# HMI.net
KiCad netlist of a schematic drawn in Altium Designer
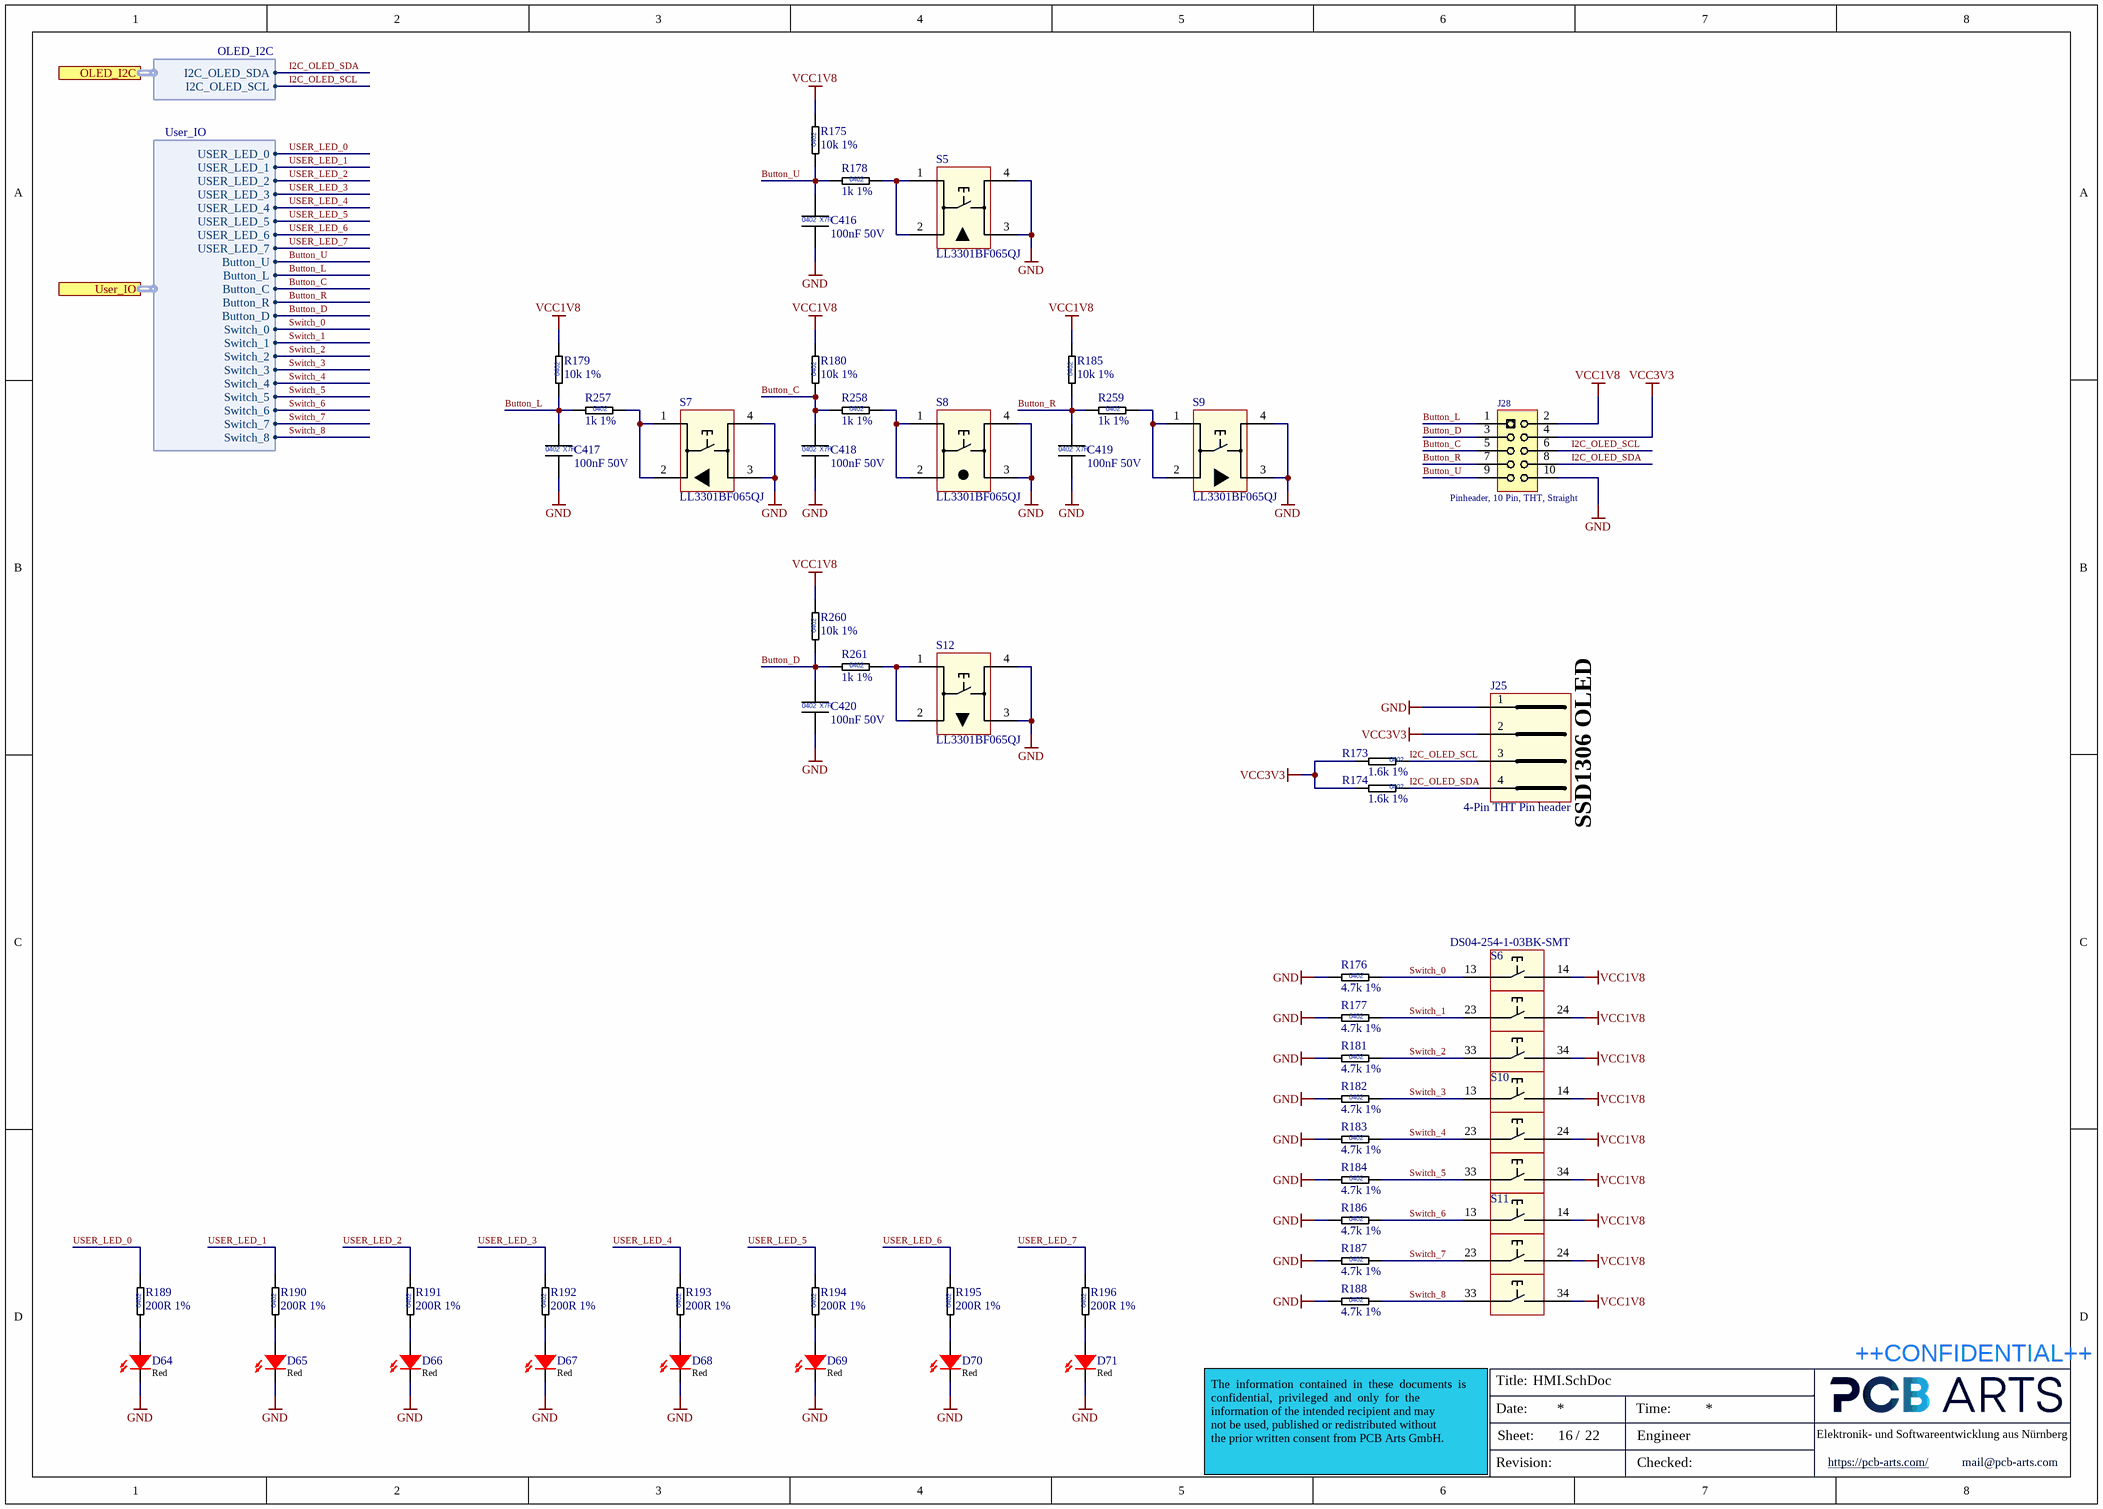
[diagram p0: HMI.SchDoc]

(export (version "E")
  (design (tool "Eeschema 10.0.6"))
  (components
    (comp (ref "C416")
      (value "100nF 50V")
      (footprint "Cap:CAP_0402_L")
      (description "Multilayer Ceramic Capacitors MLCC - SMD/SMT 0402 50VDC")
      (libsource (lib "Cap") (part "CAP_0402_100nF_50V"))
    )
    (comp (ref "C417")
      (value "100nF 50V")
      (footprint "Cap:CAP_0402_L")
      (description "Multilayer Ceramic Capacitors MLCC - SMD/SMT 0402 50VDC")
      (libsource (lib "Cap") (part "CAP_0402_100nF_50V"))
    )
    (comp (ref "C418")
      (value "100nF 50V")
      (footprint "Cap:CAP_0402_L")
      (description "Multilayer Ceramic Capacitors MLCC - SMD/SMT 0402 50VDC")
      (libsource (lib "Cap") (part "CAP_0402_100nF_50V"))
    )
    (comp (ref "C419")
      (value "100nF 50V")
      (footprint "Cap:CAP_0402_L")
      (description "Multilayer Ceramic Capacitors MLCC - SMD/SMT 0402 50VDC")
      (libsource (lib "Cap") (part "CAP_0402_100nF_50V"))
    )
    (comp (ref "C420")
      (value "100nF 50V")
      (footprint "Cap:CAP_0402_L")
      (description "Multilayer Ceramic Capacitors MLCC - SMD/SMT 0402 50VDC")
      (libsource (lib "Cap") (part "CAP_0402_100nF_50V"))
    )
    (comp (ref "D64")
      (value "LTST-S270KRKT")
      (footprint "Active:LED-0603 Sideview")
      (description "RED  0603 Light Emitting Diode")
      (fields (field (name "COLOR") "Red"))
      (libsource (lib "Active") (part "LED 0603 Red Sideview"))
    )
    (comp (ref "D65")
      (value "LTST-S270KRKT")
      (footprint "Active:LED-0603 Sideview")
      (description "RED  0603 Light Emitting Diode")
      (fields (field (name "COLOR") "Red"))
      (libsource (lib "Active") (part "LED 0603 Red Sideview"))
    )
    (comp (ref "D66")
      (value "LTST-S270KRKT")
      (footprint "Active:LED-0603 Sideview")
      (description "RED  0603 Light Emitting Diode")
      (fields (field (name "COLOR") "Red"))
      (libsource (lib "Active") (part "LED 0603 Red Sideview"))
    )
    (comp (ref "D67")
      (value "LTST-S270KRKT")
      (footprint "Active:LED-0603 Sideview")
      (description "RED  0603 Light Emitting Diode")
      (fields (field (name "COLOR") "Red"))
      (libsource (lib "Active") (part "LED 0603 Red Sideview"))
    )
    (comp (ref "D68")
      (value "LTST-S270KRKT")
      (footprint "Active:LED-0603 Sideview")
      (description "RED  0603 Light Emitting Diode")
      (fields (field (name "COLOR") "Red"))
      (libsource (lib "Active") (part "LED 0603 Red Sideview"))
    )
    (comp (ref "D69")
      (value "LTST-S270KRKT")
      (footprint "Active:LED-0603 Sideview")
      (description "RED  0603 Light Emitting Diode")
      (fields (field (name "COLOR") "Red"))
      (libsource (lib "Active") (part "LED 0603 Red Sideview"))
    )
    (comp (ref "D70")
      (value "LTST-S270KRKT")
      (footprint "Active:LED-0603 Sideview")
      (description "RED  0603 Light Emitting Diode")
      (fields (field (name "COLOR") "Red"))
      (libsource (lib "Active") (part "LED 0603 Red Sideview"))
    )
    (comp (ref "D71")
      (value "LTST-S270KRKT")
      (footprint "Active:LED-0603 Sideview")
      (description "RED  0603 Light Emitting Diode")
      (fields (field (name "COLOR") "Red"))
      (libsource (lib "Active") (part "LED 0603 Red Sideview"))
    )
    (comp (ref "J25")
      (value "4-Pin THT Pin header")
      (footprint "Conn:61300411121")
      (description "WR-PHD 2.54mm 4Pin THT Header")
      (libsource (lib "Conn") (part "61300411121_WR-PHD 2.54mm 4Pin THT Header"))
    )
    (comp (ref "J28")
      (value "Pinheader, 10 Pin, THT, Straight")
      (footprint "Conn:62701021621")
      (description "Box Pin header THT 1.27mm 10Pol Straight")
      (libsource (lib "Conn") (part "62701021621_Box Pin header THT 1.27mm 10Pol Straight"))
    )
    (comp (ref "R173")
      (value "1.6k 1%")
      (footprint "Res:RES_0402_L")
      (description "Thick Film Resistors - SMD 1.6kOhm 1%")
      (libsource (lib "Res") (part "RES_0402_1.6k_1%"))
    )
    (comp (ref "R174")
      (value "1.6k 1%")
      (footprint "Res:RES_0402_L")
      (description "Thick Film Resistors - SMD 1.6kOhm 1%")
      (libsource (lib "Res") (part "RES_0402_1.6k_1%"))
    )
    (comp (ref "R175")
      (value "10k 1%")
      (footprint "Res:RES_0402_L")
      (description "Thick Film Resistors - SMD 10kOhm 1%")
      (libsource (lib "Res") (part "RES_0402_10k_1%"))
    )
    (comp (ref "R176")
      (value "4.7k 1%")
      (footprint "Res:RES_0402_L")
      (description "Thick Film Resistors - SMD 4.7kOhm 1%")
      (libsource (lib "Res") (part "RES_0402_4.7k_1%"))
    )
    (comp (ref "R177")
      (value "4.7k 1%")
      (footprint "Res:RES_0402_L")
      (description "Thick Film Resistors - SMD 4.7kOhm 1%")
      (libsource (lib "Res") (part "RES_0402_4.7k_1%"))
    )
    (comp (ref "R178")
      (value "1k 1%")
      (footprint "Res:RES_0402_L")
      (description "Thick Film Resistors - SMD 1kOhm 1%")
      (libsource (lib "Res") (part "RES_0402_1k_1%"))
    )
    (comp (ref "R179")
      (value "10k 1%")
      (footprint "Res:RES_0402_L")
      (description "Thick Film Resistors - SMD 10kOhm 1%")
      (libsource (lib "Res") (part "RES_0402_10k_1%"))
    )
    (comp (ref "R180")
      (value "10k 1%")
      (footprint "Res:RES_0402_L")
      (description "Thick Film Resistors - SMD 10kOhm 1%")
      (libsource (lib "Res") (part "RES_0402_10k_1%"))
    )
    (comp (ref "R181")
      (value "4.7k 1%")
      (footprint "Res:RES_0402_L")
      (description "Thick Film Resistors - SMD 4.7kOhm 1%")
      (libsource (lib "Res") (part "RES_0402_4.7k_1%"))
    )
    (comp (ref "R182")
      (value "4.7k 1%")
      (footprint "Res:RES_0402_L")
      (description "Thick Film Resistors - SMD 4.7kOhm 1%")
      (libsource (lib "Res") (part "RES_0402_4.7k_1%"))
    )
    (comp (ref "R183")
      (value "4.7k 1%")
      (footprint "Res:RES_0402_L")
      (description "Thick Film Resistors - SMD 4.7kOhm 1%")
      (libsource (lib "Res") (part "RES_0402_4.7k_1%"))
    )
    (comp (ref "R184")
      (value "4.7k 1%")
      (footprint "Res:RES_0402_L")
      (description "Thick Film Resistors - SMD 4.7kOhm 1%")
      (libsource (lib "Res") (part "RES_0402_4.7k_1%"))
    )
    (comp (ref "R185")
      (value "10k 1%")
      (footprint "Res:RES_0402_L")
      (description "Thick Film Resistors - SMD 10kOhm 1%")
      (libsource (lib "Res") (part "RES_0402_10k_1%"))
    )
    (comp (ref "R186")
      (value "4.7k 1%")
      (footprint "Res:RES_0402_L")
      (description "Thick Film Resistors - SMD 4.7kOhm 1%")
      (libsource (lib "Res") (part "RES_0402_4.7k_1%"))
    )
    (comp (ref "R187")
      (value "4.7k 1%")
      (footprint "Res:RES_0402_L")
      (description "Thick Film Resistors - SMD 4.7kOhm 1%")
      (libsource (lib "Res") (part "RES_0402_4.7k_1%"))
    )
    (comp (ref "R188")
      (value "4.7k 1%")
      (footprint "Res:RES_0402_L")
      (description "Thick Film Resistors - SMD 4.7kOhm 1%")
      (libsource (lib "Res") (part "RES_0402_4.7k_1%"))
    )
    (comp (ref "R189")
      (value "200R 1%")
      (footprint "Res:RES_0402_L")
      (description "Thick Film Resistors - SMD 200Ohm 1%")
      (libsource (lib "Res") (part "RES_0402_200R 1%"))
    )
    (comp (ref "R190")
      (value "200R 1%")
      (footprint "Res:RES_0402_L")
      (description "Thick Film Resistors - SMD 200Ohm 1%")
      (libsource (lib "Res") (part "RES_0402_200R 1%"))
    )
    (comp (ref "R191")
      (value "200R 1%")
      (footprint "Res:RES_0402_L")
      (description "Thick Film Resistors - SMD 200Ohm 1%")
      (libsource (lib "Res") (part "RES_0402_200R 1%"))
    )
    (comp (ref "R192")
      (value "200R 1%")
      (footprint "Res:RES_0402_L")
      (description "Thick Film Resistors - SMD 200Ohm 1%")
      (libsource (lib "Res") (part "RES_0402_200R 1%"))
    )
    (comp (ref "R193")
      (value "200R 1%")
      (footprint "Res:RES_0402_L")
      (description "Thick Film Resistors - SMD 200Ohm 1%")
      (libsource (lib "Res") (part "RES_0402_200R 1%"))
    )
    (comp (ref "R194")
      (value "200R 1%")
      (footprint "Res:RES_0402_L")
      (description "Thick Film Resistors - SMD 200Ohm 1%")
      (libsource (lib "Res") (part "RES_0402_200R 1%"))
    )
    (comp (ref "R195")
      (value "200R 1%")
      (footprint "Res:RES_0402_L")
      (description "Thick Film Resistors - SMD 200Ohm 1%")
      (libsource (lib "Res") (part "RES_0402_200R 1%"))
    )
    (comp (ref "R196")
      (value "200R 1%")
      (footprint "Res:RES_0402_L")
      (description "Thick Film Resistors - SMD 200Ohm 1%")
      (libsource (lib "Res") (part "RES_0402_200R 1%"))
    )
    (comp (ref "R257")
      (value "1k 1%")
      (footprint "Res:RES_0402_L")
      (description "Thick Film Resistors - SMD 1kOhm 1%")
      (libsource (lib "Res") (part "RES_0402_1k_1%"))
    )
    (comp (ref "R258")
      (value "1k 1%")
      (footprint "Res:RES_0402_L")
      (description "Thick Film Resistors - SMD 1kOhm 1%")
      (libsource (lib "Res") (part "RES_0402_1k_1%"))
    )
    (comp (ref "R259")
      (value "1k 1%")
      (footprint "Res:RES_0402_L")
      (description "Thick Film Resistors - SMD 1kOhm 1%")
      (libsource (lib "Res") (part "RES_0402_1k_1%"))
    )
    (comp (ref "R260")
      (value "10k 1%")
      (footprint "Res:RES_0402_L")
      (description "Thick Film Resistors - SMD 10kOhm 1%")
      (libsource (lib "Res") (part "RES_0402_10k_1%"))
    )
    (comp (ref "R261")
      (value "1k 1%")
      (footprint "Res:RES_0402_L")
      (description "Thick Film Resistors - SMD 1kOhm 1%")
      (libsource (lib "Res") (part "RES_0402_1k_1%"))
    )
    (comp (ref "S5")
      (value "LL3301BF065QJ")
      (footprint "Electro_Mech:LL3301BF065QJ")
      (description "SPST Top Actuated  Button, 65gf, SMD h: 9.8mm")
      (libsource (lib "Electro_Mech") (part "LL3301BF065QJ_SPST Top Actuated  Button, 65gf, SMD h{colon} 9.8mm"))
    )
    (comp (ref "S6")
      (value "DS04-254-1-03BK-SMT")
      (footprint "Electro_Mech:CUI DS04-254-SMT Series, 3 Pole")
      (description "SMD DIP Switch, 3 Pos, Slide actuator")
      (libsource (lib "Electro_Mech") (part "DS04-254-1-03BK-SMT"))
    )
    (comp (ref "S7")
      (value "LL3301BF065QJ")
      (footprint "Electro_Mech:LL3301BF065QJ")
      (description "SPST Top Actuated  Button, 65gf, SMD h: 9.8mm")
      (libsource (lib "Electro_Mech") (part "LL3301BF065QJ_SPST Top Actuated  Button, 65gf, SMD h{colon} 9.8mm"))
    )
    (comp (ref "S8")
      (value "LL3301BF065QJ")
      (footprint "Electro_Mech:LL3301BF065QJ")
      (description "SPST Top Actuated  Button, 65gf, SMD h: 9.8mm")
      (libsource (lib "Electro_Mech") (part "LL3301BF065QJ_SPST Top Actuated  Button, 65gf, SMD h{colon} 9.8mm"))
    )
    (comp (ref "S9")
      (value "LL3301BF065QJ")
      (footprint "Electro_Mech:LL3301BF065QJ")
      (description "SPST Top Actuated  Button, 65gf, SMD h: 9.8mm")
      (libsource (lib "Electro_Mech") (part "LL3301BF065QJ_SPST Top Actuated  Button, 65gf, SMD h{colon} 9.8mm"))
    )
    (comp (ref "S10")
      (value "DS04-254-1-03BK-SMT")
      (footprint "Electro_Mech:CUI DS04-254-SMT Series, 3 Pole")
      (description "SMD DIP Switch, 3 Pos, Slide actuator")
      (libsource (lib "Electro_Mech") (part "DS04-254-1-03BK-SMT"))
    )
    (comp (ref "S11")
      (value "DS04-254-1-03BK-SMT")
      (footprint "Electro_Mech:CUI DS04-254-SMT Series, 3 Pole")
      (description "SMD DIP Switch, 3 Pos, Slide actuator")
      (libsource (lib "Electro_Mech") (part "DS04-254-1-03BK-SMT"))
    )
    (comp (ref "S12")
      (value "LL3301BF065QJ")
      (footprint "Electro_Mech:LL3301BF065QJ")
      (description "SPST Top Actuated  Button, 65gf, SMD h: 9.8mm")
      (libsource (lib "Electro_Mech") (part "LL3301BF065QJ_SPST Top Actuated  Button, 65gf, SMD h{colon} 9.8mm"))
    )
  )
  (nets
    (net (code "3") (name "/Button_C") (class "Default")
      (node (ref "C418") (pin "1") (pinfunction "1_1") (pintype "passive"))
      (node (ref "J28") (pin "5") (pinfunction "5_5") (pintype "passive"))
      (node (ref "R180") (pin "1") (pinfunction "1_1") (pintype "passive"))
      (node (ref "R258") (pin "1") (pinfunction "1_1") (pintype "passive"))
    )
    (net (code "4") (name "/Button_D") (class "Default")
      (node (ref "C420") (pin "1") (pinfunction "1_1") (pintype "passive"))
      (node (ref "J28") (pin "3") (pinfunction "3_3") (pintype "passive"))
      (node (ref "R260") (pin "1") (pinfunction "1_1") (pintype "passive"))
      (node (ref "R261") (pin "1") (pinfunction "1_1") (pintype "passive"))
    )
    (net (code "5") (name "/Button_L") (class "Default")
      (node (ref "C417") (pin "1") (pinfunction "1_1") (pintype "passive"))
      (node (ref "J28") (pin "1") (pinfunction "1_1") (pintype "passive"))
      (node (ref "R179") (pin "1") (pinfunction "1_1") (pintype "passive"))
      (node (ref "R257") (pin "1") (pinfunction "1_1") (pintype "passive"))
    )
    (net (code "6") (name "/Button_R") (class "Default")
      (node (ref "C419") (pin "1") (pinfunction "1_1") (pintype "passive"))
      (node (ref "J28") (pin "7") (pinfunction "7_7") (pintype "passive"))
      (node (ref "R185") (pin "1") (pinfunction "1_1") (pintype "passive"))
      (node (ref "R259") (pin "1") (pinfunction "1_1") (pintype "passive"))
    )
    (net (code "7") (name "/Button_U") (class "Default")
      (node (ref "C416") (pin "1") (pinfunction "1_1") (pintype "passive"))
      (node (ref "J28") (pin "9") (pinfunction "9_9") (pintype "passive"))
      (node (ref "R175") (pin "1") (pinfunction "1_1") (pintype "passive"))
      (node (ref "R178") (pin "1") (pinfunction "1_1") (pintype "passive"))
    )
    (net (code "8") (name "/I2C_OLED_SCL") (class "Default")
      (node (ref "J25") (pin "3") (pinfunction "3_3") (pintype "passive"))
      (node (ref "J28") (pin "6") (pinfunction "6_6") (pintype "passive"))
      (node (ref "R173") (pin "1") (pinfunction "1_1") (pintype "passive"))
    )
    (net (code "9") (name "/I2C_OLED_SDA") (class "Default")
      (node (ref "J25") (pin "4") (pinfunction "4_4") (pintype "passive"))
      (node (ref "J28") (pin "8") (pinfunction "8_8") (pintype "passive"))
      (node (ref "R174") (pin "1") (pinfunction "1_1") (pintype "passive"))
    )
    (net (code "10") (name "/Switch_0") (class "Default")
      (node (ref "R176") (pin "2") (pinfunction "2_2") (pintype "passive"))
      (node (ref "S6") (pin "13") (pinfunction "13_13") (pintype "passive"))
    )
    (net (code "11") (name "/Switch_1") (class "Default")
      (node (ref "R177") (pin "2") (pinfunction "2_2") (pintype "passive"))
      (node (ref "S6") (pin "23") (pinfunction "23_23") (pintype "passive"))
    )
    (net (code "12") (name "/Switch_2") (class "Default")
      (node (ref "R181") (pin "2") (pinfunction "2_2") (pintype "passive"))
      (node (ref "S6") (pin "33") (pinfunction "33_33") (pintype "passive"))
    )
    (net (code "13") (name "/Switch_3") (class "Default")
      (node (ref "R182") (pin "2") (pinfunction "2_2") (pintype "passive"))
      (node (ref "S10") (pin "13") (pinfunction "13_13") (pintype "passive"))
    )
    (net (code "14") (name "/Switch_4") (class "Default")
      (node (ref "R183") (pin "2") (pinfunction "2_2") (pintype "passive"))
      (node (ref "S10") (pin "23") (pinfunction "23_23") (pintype "passive"))
    )
    (net (code "15") (name "/Switch_5") (class "Default")
      (node (ref "R184") (pin "2") (pinfunction "2_2") (pintype "passive"))
      (node (ref "S10") (pin "33") (pinfunction "33_33") (pintype "passive"))
    )
    (net (code "16") (name "/Switch_6") (class "Default")
      (node (ref "R186") (pin "2") (pinfunction "2_2") (pintype "passive"))
      (node (ref "S11") (pin "13") (pinfunction "13_13") (pintype "passive"))
    )
    (net (code "17") (name "/Switch_7") (class "Default")
      (node (ref "R187") (pin "2") (pinfunction "2_2") (pintype "passive"))
      (node (ref "S11") (pin "23") (pinfunction "23_23") (pintype "passive"))
    )
    (net (code "18") (name "/Switch_8") (class "Default")
      (node (ref "R188") (pin "2") (pinfunction "2_2") (pintype "passive"))
      (node (ref "S11") (pin "33") (pinfunction "33_33") (pintype "passive"))
    )
    (net (code "19") (name "/USER_LED_0") (class "Default")
      (node (ref "R189") (pin "2") (pinfunction "2_2") (pintype "passive"))
    )
    (net (code "20") (name "/USER_LED_1") (class "Default")
      (node (ref "R190") (pin "2") (pinfunction "2_2") (pintype "passive"))
    )
    (net (code "21") (name "/USER_LED_2") (class "Default")
      (node (ref "R191") (pin "2") (pinfunction "2_2") (pintype "passive"))
    )
    (net (code "22") (name "/USER_LED_3") (class "Default")
      (node (ref "R192") (pin "2") (pinfunction "2_2") (pintype "passive"))
    )
    (net (code "23") (name "/USER_LED_4") (class "Default")
      (node (ref "R193") (pin "2") (pinfunction "2_2") (pintype "passive"))
    )
    (net (code "24") (name "/USER_LED_5") (class "Default")
      (node (ref "R194") (pin "2") (pinfunction "2_2") (pintype "passive"))
    )
    (net (code "25") (name "/USER_LED_6") (class "Default")
      (node (ref "R195") (pin "2") (pinfunction "2_2") (pintype "passive"))
    )
    (net (code "26") (name "/USER_LED_7") (class "Default")
      (node (ref "R196") (pin "2") (pinfunction "2_2") (pintype "passive"))
    )
    (net (code "29") (name "GND") (class "Default")
      (node (ref "C416") (pin "2") (pinfunction "2_2") (pintype "passive"))
      (node (ref "C417") (pin "2") (pinfunction "2_2") (pintype "passive"))
      (node (ref "C418") (pin "2") (pinfunction "2_2") (pintype "passive"))
      (node (ref "C419") (pin "2") (pinfunction "2_2") (pintype "passive"))
      (node (ref "C420") (pin "2") (pinfunction "2_2") (pintype "passive"))
      (node (ref "D64") (pin "1") (pinfunction "1_1") (pintype "passive"))
      (node (ref "D65") (pin "1") (pinfunction "1_1") (pintype "passive"))
      (node (ref "D66") (pin "1") (pinfunction "1_1") (pintype "passive"))
      (node (ref "D67") (pin "1") (pinfunction "1_1") (pintype "passive"))
      (node (ref "D68") (pin "1") (pinfunction "1_1") (pintype "passive"))
      (node (ref "D69") (pin "1") (pinfunction "1_1") (pintype "passive"))
      (node (ref "D70") (pin "1") (pinfunction "1_1") (pintype "passive"))
      (node (ref "D71") (pin "1") (pinfunction "1_1") (pintype "passive"))
      (node (ref "J25") (pin "1") (pinfunction "1_1") (pintype "passive"))
      (node (ref "J28") (pin "10") (pinfunction "10_10") (pintype "passive"))
      (node (ref "R176") (pin "1") (pinfunction "1_1") (pintype "passive"))
      (node (ref "R177") (pin "1") (pinfunction "1_1") (pintype "passive"))
      (node (ref "R181") (pin "1") (pinfunction "1_1") (pintype "passive"))
      (node (ref "R182") (pin "1") (pinfunction "1_1") (pintype "passive"))
      (node (ref "R183") (pin "1") (pinfunction "1_1") (pintype "passive"))
      (node (ref "R184") (pin "1") (pinfunction "1_1") (pintype "passive"))
      (node (ref "R186") (pin "1") (pinfunction "1_1") (pintype "passive"))
      (node (ref "R187") (pin "1") (pinfunction "1_1") (pintype "passive"))
      (node (ref "R188") (pin "1") (pinfunction "1_1") (pintype "passive"))
      (node (ref "S12") (pin "3") (pinfunction "3_3") (pintype "passive"))
      (node (ref "S12") (pin "4") (pinfunction "4_4") (pintype "passive"))
      (node (ref "S5") (pin "3") (pinfunction "3_3") (pintype "passive"))
      (node (ref "S5") (pin "4") (pinfunction "4_4") (pintype "passive"))
      (node (ref "S7") (pin "3") (pinfunction "3_3") (pintype "passive"))
      (node (ref "S7") (pin "4") (pinfunction "4_4") (pintype "passive"))
      (node (ref "S8") (pin "3") (pinfunction "3_3") (pintype "passive"))
      (node (ref "S8") (pin "4") (pinfunction "4_4") (pintype "passive"))
      (node (ref "S9") (pin "3") (pinfunction "3_3") (pintype "passive"))
      (node (ref "S9") (pin "4") (pinfunction "4_4") (pintype "passive"))
    )
    (net (code "30") (name "Net-(D64-Pad2)") (class "Default")
      (node (ref "D64") (pin "2") (pinfunction "2_2") (pintype "passive"))
      (node (ref "R189") (pin "1") (pinfunction "1_1") (pintype "passive"))
    )
    (net (code "31") (name "Net-(D65-Pad2)") (class "Default")
      (node (ref "D65") (pin "2") (pinfunction "2_2") (pintype "passive"))
      (node (ref "R190") (pin "1") (pinfunction "1_1") (pintype "passive"))
    )
    (net (code "32") (name "Net-(D66-Pad2)") (class "Default")
      (node (ref "D66") (pin "2") (pinfunction "2_2") (pintype "passive"))
      (node (ref "R191") (pin "1") (pinfunction "1_1") (pintype "passive"))
    )
    (net (code "33") (name "Net-(D67-Pad2)") (class "Default")
      (node (ref "D67") (pin "2") (pinfunction "2_2") (pintype "passive"))
      (node (ref "R192") (pin "1") (pinfunction "1_1") (pintype "passive"))
    )
    (net (code "34") (name "Net-(D68-Pad2)") (class "Default")
      (node (ref "D68") (pin "2") (pinfunction "2_2") (pintype "passive"))
      (node (ref "R193") (pin "1") (pinfunction "1_1") (pintype "passive"))
    )
    (net (code "35") (name "Net-(D69-Pad2)") (class "Default")
      (node (ref "D69") (pin "2") (pinfunction "2_2") (pintype "passive"))
      (node (ref "R194") (pin "1") (pinfunction "1_1") (pintype "passive"))
    )
    (net (code "36") (name "Net-(D70-Pad2)") (class "Default")
      (node (ref "D70") (pin "2") (pinfunction "2_2") (pintype "passive"))
      (node (ref "R195") (pin "1") (pinfunction "1_1") (pintype "passive"))
    )
    (net (code "37") (name "Net-(D71-Pad2)") (class "Default")
      (node (ref "D71") (pin "2") (pinfunction "2_2") (pintype "passive"))
      (node (ref "R196") (pin "1") (pinfunction "1_1") (pintype "passive"))
    )
    (net (code "38") (name "Net-(R178-Pad2)") (class "Default")
      (node (ref "R178") (pin "2") (pinfunction "2_2") (pintype "passive"))
      (node (ref "S5") (pin "1") (pinfunction "1_1") (pintype "passive"))
      (node (ref "S5") (pin "2") (pinfunction "2_2") (pintype "passive"))
    )
    (net (code "39") (name "Net-(R257-Pad2)") (class "Default")
      (node (ref "R257") (pin "2") (pinfunction "2_2") (pintype "passive"))
      (node (ref "S7") (pin "1") (pinfunction "1_1") (pintype "passive"))
      (node (ref "S7") (pin "2") (pinfunction "2_2") (pintype "passive"))
    )
    (net (code "40") (name "Net-(R258-Pad2)") (class "Default")
      (node (ref "R258") (pin "2") (pinfunction "2_2") (pintype "passive"))
      (node (ref "S8") (pin "1") (pinfunction "1_1") (pintype "passive"))
      (node (ref "S8") (pin "2") (pinfunction "2_2") (pintype "passive"))
    )
    (net (code "41") (name "Net-(R259-Pad2)") (class "Default")
      (node (ref "R259") (pin "2") (pinfunction "2_2") (pintype "passive"))
      (node (ref "S9") (pin "1") (pinfunction "1_1") (pintype "passive"))
      (node (ref "S9") (pin "2") (pinfunction "2_2") (pintype "passive"))
    )
    (net (code "42") (name "Net-(R261-Pad2)") (class "Default")
      (node (ref "R261") (pin "2") (pinfunction "2_2") (pintype "passive"))
      (node (ref "S12") (pin "1") (pinfunction "1_1") (pintype "passive"))
      (node (ref "S12") (pin "2") (pinfunction "2_2") (pintype "passive"))
    )
    (net (code "43") (name "VCC1V8") (class "Default")
      (node (ref "J28") (pin "2") (pinfunction "2_2") (pintype "passive"))
      (node (ref "R175") (pin "2") (pinfunction "2_2") (pintype "passive"))
      (node (ref "R179") (pin "2") (pinfunction "2_2") (pintype "passive"))
      (node (ref "R180") (pin "2") (pinfunction "2_2") (pintype "passive"))
      (node (ref "R185") (pin "2") (pinfunction "2_2") (pintype "passive"))
      (node (ref "R260") (pin "2") (pinfunction "2_2") (pintype "passive"))
      (node (ref "S10") (pin "14") (pinfunction "14_14") (pintype "passive"))
      (node (ref "S10") (pin "24") (pinfunction "24_24") (pintype "passive"))
      (node (ref "S10") (pin "34") (pinfunction "34_34") (pintype "passive"))
      (node (ref "S11") (pin "14") (pinfunction "14_14") (pintype "passive"))
      (node (ref "S11") (pin "24") (pinfunction "24_24") (pintype "passive"))
      (node (ref "S11") (pin "34") (pinfunction "34_34") (pintype "passive"))
      (node (ref "S6") (pin "14") (pinfunction "14_14") (pintype "passive"))
      (node (ref "S6") (pin "24") (pinfunction "24_24") (pintype "passive"))
      (node (ref "S6") (pin "34") (pinfunction "34_34") (pintype "passive"))
    )
    (net (code "44") (name "VCC3V3") (class "Default")
      (node (ref "J25") (pin "2") (pinfunction "2_2") (pintype "passive"))
      (node (ref "J28") (pin "4") (pinfunction "4_4") (pintype "passive"))
      (node (ref "R173") (pin "2") (pinfunction "2_2") (pintype "passive"))
      (node (ref "R174") (pin "2") (pinfunction "2_2") (pintype "passive"))
    )
  )
)
